# HammondWizard.net
KiCad netlist of a schematic drawn in EAGLE
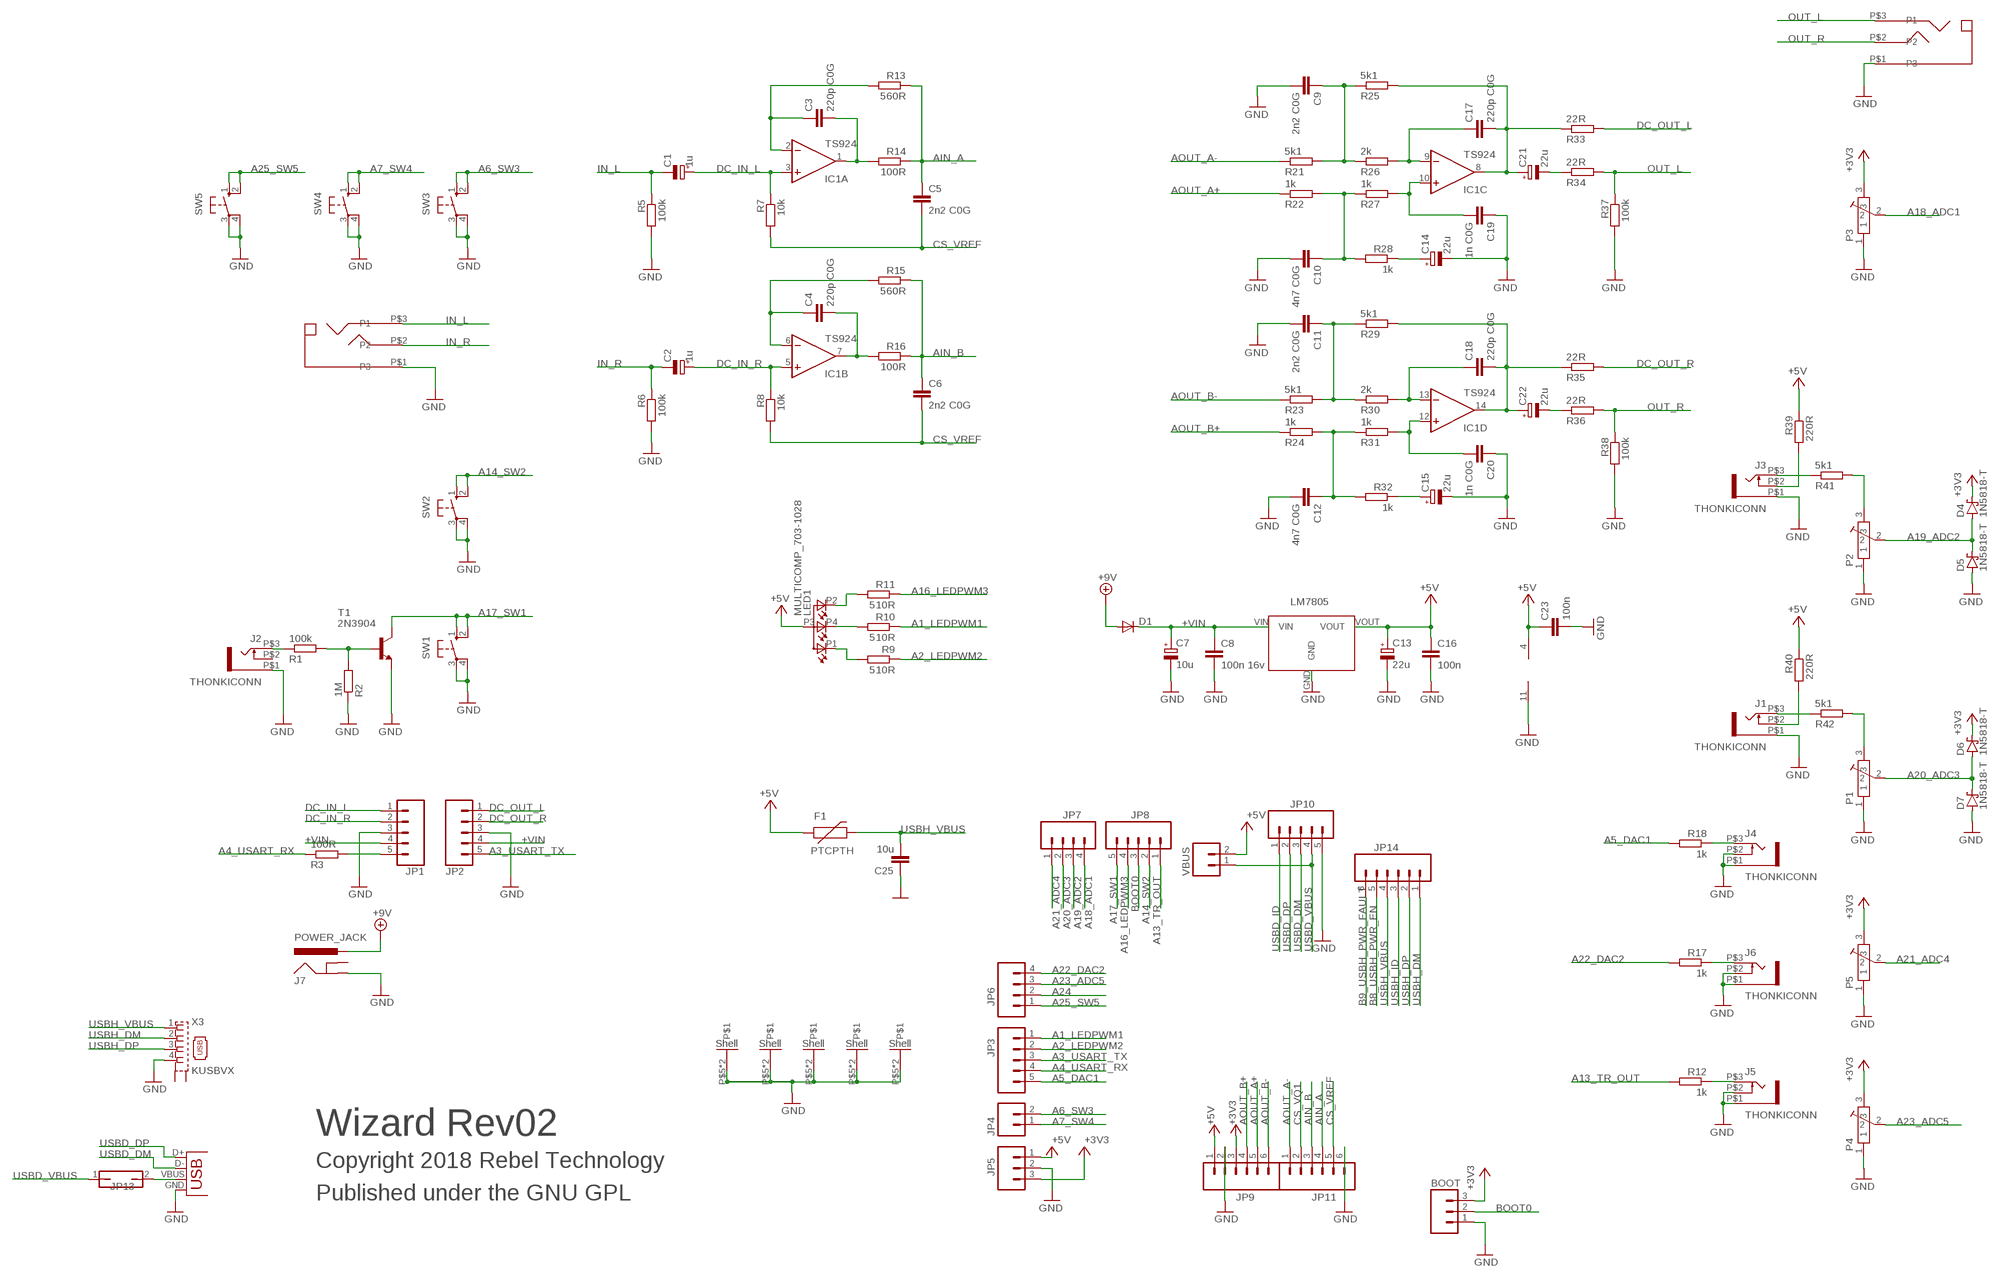
[diagram p0: schematic, sheet 1]

(export (version "E")
  (design (tool "Eeschema 10.0.6"))
  (components
    (comp (ref "BOOT")
      (value "M03PTH")
      (footprint "eagle-import:1X03")
      (libsource (lib "eagle-import") (part "M03PTH"))
    )
    (comp (ref "C1")
      (value "1u")
      (footprint "eagle-import:E5-6")
      (libsource (lib "eagle-import") (part "CPOL-EUE5-6"))
    )
    (comp (ref "C2")
      (value "1u")
      (footprint "eagle-import:E5-6")
      (libsource (lib "eagle-import") (part "CPOL-EUE5-6"))
    )
    (comp (ref "C3")
      (value "220p C0G")
      (footprint "eagle-import:C050-024X044")
      (libsource (lib "eagle-import") (part "resistor_C-EU050-024X044"))
    )
    (comp (ref "C4")
      (value "220p C0G")
      (footprint "eagle-import:C050-024X044")
      (libsource (lib "eagle-import") (part "resistor_C-EU050-024X044"))
    )
    (comp (ref "C5")
      (value "2n2 C0G")
      (footprint "eagle-import:C050-024X044")
      (libsource (lib "eagle-import") (part "resistor_C-EU050-024X044"))
    )
    (comp (ref "C6")
      (value "2n2 C0G")
      (footprint "eagle-import:C050-024X044")
      (libsource (lib "eagle-import") (part "resistor_C-EU050-024X044"))
    )
    (comp (ref "C7")
      (value "10u")
      (footprint "eagle-import:E5-6")
      (libsource (lib "eagle-import") (part "CPOL-EUE5-6"))
    )
    (comp (ref "C8")
      (value "100n 16v")
      (footprint "eagle-import:C050-024X044")
      (libsource (lib "eagle-import") (part "C-EU050-024X044"))
    )
    (comp (ref "C9")
      (value "2n2 C0G")
      (footprint "eagle-import:C050-024X044")
      (libsource (lib "eagle-import") (part "resistor_C-EU050-024X044"))
    )
    (comp (ref "C10")
      (value "4n7 C0G")
      (footprint "eagle-import:C050-024X044")
      (libsource (lib "eagle-import") (part "resistor_C-EU050-024X044"))
    )
    (comp (ref "C11")
      (value "2n2 C0G")
      (footprint "eagle-import:C050-024X044")
      (libsource (lib "eagle-import") (part "resistor_C-EU050-024X044"))
    )
    (comp (ref "C12")
      (value "4n7 C0G")
      (footprint "eagle-import:C050-024X044")
      (libsource (lib "eagle-import") (part "resistor_C-EU050-024X044"))
    )
    (comp (ref "C13")
      (value "22u")
      (footprint "eagle-import:E5-6")
      (libsource (lib "eagle-import") (part "CPOL-EUE5-6"))
    )
    (comp (ref "C14")
      (value "22u")
      (footprint "eagle-import:E5-6")
      (libsource (lib "eagle-import") (part "CPOL-EUE5-6"))
    )
    (comp (ref "C15")
      (value "22u")
      (footprint "eagle-import:E5-6")
      (libsource (lib "eagle-import") (part "CPOL-EUE5-6"))
    )
    (comp (ref "C16")
      (value "100n")
      (footprint "eagle-import:C050-024X044")
      (libsource (lib "eagle-import") (part "C-EU050-024X044"))
    )
    (comp (ref "C17")
      (value "220p C0G")
      (footprint "eagle-import:C050-024X044")
      (libsource (lib "eagle-import") (part "resistor_C-EU050-024X044"))
    )
    (comp (ref "C18")
      (value "220p C0G")
      (footprint "eagle-import:C050-024X044")
      (libsource (lib "eagle-import") (part "resistor_C-EU050-024X044"))
    )
    (comp (ref "C19")
      (value "1n C0G")
      (footprint "eagle-import:C050-024X044")
      (libsource (lib "eagle-import") (part "resistor_C-EU050-024X044"))
    )
    (comp (ref "C20")
      (value "1n C0G")
      (footprint "eagle-import:C050-024X044")
      (libsource (lib "eagle-import") (part "resistor_C-EU050-024X044"))
    )
    (comp (ref "C21")
      (value "22u")
      (footprint "eagle-import:E5-6")
      (libsource (lib "eagle-import") (part "CPOL-EUE5-6"))
    )
    (comp (ref "C22")
      (value "22u")
      (footprint "eagle-import:E5-6")
      (libsource (lib "eagle-import") (part "CPOL-EUE5-6"))
    )
    (comp (ref "C23")
      (value "100n")
      (footprint "eagle-import:C050-024X044")
      (libsource (lib "eagle-import") (part "resistor_C-EU050-024X044"))
    )
    (comp (ref "C25")
      (value "10u")
      (footprint "eagle-import:C050-024X044")
      (libsource (lib "eagle-import") (part "resistor_C-EU050-024X044"))
    )
    (comp (ref "D1")
      (value "DIODE1N4001")
      (footprint "eagle-import:DIODE-1N4001")
      (libsource (lib "eagle-import") (part "DIODE1N4001"))
    )
    (comp (ref "D4")
      (value "1N5818-T")
      (footprint "eagle-import:DO41-7.6")
      (libsource (lib "eagle-import") (part "1N5818-T"))
    )
    (comp (ref "D5")
      (value "1N5818-T")
      (footprint "eagle-import:DO41-7.6")
      (libsource (lib "eagle-import") (part "1N5818-T"))
    )
    (comp (ref "D6")
      (value "1N5818-T")
      (footprint "eagle-import:DO41-7.6")
      (libsource (lib "eagle-import") (part "1N5818-T"))
    )
    (comp (ref "D7")
      (value "1N5818-T")
      (footprint "eagle-import:DO41-7.6")
      (libsource (lib "eagle-import") (part "1N5818-T"))
    )
    (comp (ref "F1")
      (value "PTCPTH")
      (footprint "eagle-import:PTC")
      (libsource (lib "eagle-import") (part "PTCPTH"))
    )
    (comp (ref "IC1")
      (value "TS924")
      (footprint "eagle-import:DIL14")
      (libsource (lib "eagle-import") (part "LM324N"))
    )
    (comp (ref "J1")
      (value "THONKICONN")
      (footprint "eagle-import:THONKICONN")
      (libsource (lib "eagle-import") (part "THONKICONN"))
    )
    (comp (ref "J2")
      (value "THONKICONN")
      (footprint "eagle-import:THONKICONN")
      (libsource (lib "eagle-import") (part "THONKICONN"))
    )
    (comp (ref "J3")
      (value "THONKICONN")
      (footprint "eagle-import:THONKICONN")
      (libsource (lib "eagle-import") (part "THONKICONN"))
    )
    (comp (ref "J4")
      (value "THONKICONN")
      (footprint "eagle-import:THONKICONN")
      (libsource (lib "eagle-import") (part "THONKICONN"))
    )
    (comp (ref "J5")
      (value "THONKICONN")
      (footprint "eagle-import:THONKICONN")
      (libsource (lib "eagle-import") (part "THONKICONN"))
    )
    (comp (ref "J6")
      (value "THONKICONN")
      (footprint "eagle-import:THONKICONN")
      (libsource (lib "eagle-import") (part "THONKICONN"))
    )
    (comp (ref "J7")
      (value "POWER_JACK")
      (footprint "eagle-import:DC_JACK_SLOT")
      (libsource (lib "eagle-import") (part "POWER_JACK"))
    )
    (comp (ref "JP1")
      (value "CONN_05JST-VERT")
      (footprint "eagle-import:JST-5-PTH-VERT")
      (libsource (lib "eagle-import") (part "CONN_05JST-VERT"))
    )
    (comp (ref "JP2")
      (value "CONN_05JST-VERT")
      (footprint "eagle-import:JST-5-PTH-VERT")
      (libsource (lib "eagle-import") (part "CONN_05JST-VERT"))
    )
    (comp (ref "JP3")
      (value "M05PTH")
      (footprint "eagle-import:1X05")
      (libsource (lib "eagle-import") (part "M05PTH"))
    )
    (comp (ref "JP4")
      (value "M02PTH")
      (footprint "eagle-import:1X02")
      (libsource (lib "eagle-import") (part "M02PTH"))
    )
    (comp (ref "JP5")
      (value "M03PTH")
      (footprint "eagle-import:1X03")
      (libsource (lib "eagle-import") (part "M03PTH"))
    )
    (comp (ref "JP6")
      (value "M04PTH")
      (footprint "eagle-import:1X04")
      (libsource (lib "eagle-import") (part "M04PTH"))
    )
    (comp (ref "JP7")
      (value "M04PTH")
      (footprint "eagle-import:1X04")
      (libsource (lib "eagle-import") (part "M04PTH"))
    )
    (comp (ref "JP8")
      (value "M05PTH")
      (footprint "eagle-import:1X05")
      (libsource (lib "eagle-import") (part "M05PTH"))
    )
    (comp (ref "JP9")
      (value "M06SIP")
      (footprint "eagle-import:1X06")
      (libsource (lib "eagle-import") (part "M06SIP"))
    )
    (comp (ref "JP10")
      (value "M05PTH")
      (footprint "eagle-import:1X05")
      (libsource (lib "eagle-import") (part "M05PTH"))
    )
    (comp (ref "JP11")
      (value "M06SIP")
      (footprint "eagle-import:1X06")
      (libsource (lib "eagle-import") (part "M06SIP"))
    )
    (comp (ref "JP13")
      (value "JP1Q")
      (footprint "eagle-import:JP1")
      (libsource (lib "eagle-import") (part "JP1Q"))
    )
    (comp (ref "JP14")
      (value "M06SIP")
      (footprint "eagle-import:1X06")
      (libsource (lib "eagle-import") (part "M06SIP"))
    )
    (comp (ref "LED1")
      (value "MULTICOMP_703-1028")
      (footprint "eagle-import:RGB-LED-703-1028")
      (libsource (lib "eagle-import") (part "MULTICOMP_703-1028"))
    )
    (comp (ref "P1")
      (value "POT-ALPS-RK09L1140")
      (footprint "eagle-import:POT-ALPS-RK09L1140")
      (libsource (lib "eagle-import") (part "POT-ALPS-RK09L1140"))
    )
    (comp (ref "P2")
      (value "POT-ALPS-RK09L1140")
      (footprint "eagle-import:POT-ALPS-RK09L1140")
      (libsource (lib "eagle-import") (part "POT-ALPS-RK09L1140"))
    )
    (comp (ref "P3")
      (value "POT-ALPS-RK09L1140")
      (footprint "eagle-import:POT-ALPS-RK09L1140")
      (libsource (lib "eagle-import") (part "POT-ALPS-RK09L1140"))
    )
    (comp (ref "P4")
      (value "POT-ALPS-RK09L1140")
      (footprint "eagle-import:POT-ALPS-RK09L1140")
      (libsource (lib "eagle-import") (part "POT-ALPS-RK09L1140"))
    )
    (comp (ref "P5")
      (value "POT-ALPS-RK09L1140")
      (footprint "eagle-import:POT-ALPS-RK09L1140")
      (libsource (lib "eagle-import") (part "POT-ALPS-RK09L1140"))
    )
    (comp (ref "R1")
      (value "100k")
      (footprint "eagle-import:0204_7")
      (libsource (lib "eagle-import") (part "R-EU_0204/7"))
    )
    (comp (ref "R2")
      (value "1M")
      (footprint "eagle-import:0204_7")
      (libsource (lib "eagle-import") (part "R-EU_0204/7"))
    )
    (comp (ref "R3")
      (value "100R")
      (footprint "eagle-import:0204_7")
      (libsource (lib "eagle-import") (part "R-EU_0204/7"))
    )
    (comp (ref "R5")
      (value "100k")
      (footprint "eagle-import:0204_7")
      (libsource (lib "eagle-import") (part "R-EU_0204/7"))
    )
    (comp (ref "R6")
      (value "100k")
      (footprint "eagle-import:0204_7")
      (libsource (lib "eagle-import") (part "R-EU_0204/7"))
    )
    (comp (ref "R7")
      (value "10k")
      (footprint "eagle-import:0204_7")
      (libsource (lib "eagle-import") (part "R-EU_0204/7"))
    )
    (comp (ref "R8")
      (value "10k")
      (footprint "eagle-import:0204_7")
      (libsource (lib "eagle-import") (part "R-EU_0204/7"))
    )
    (comp (ref "R9")
      (value "510R")
      (footprint "eagle-import:0204_7")
      (libsource (lib "eagle-import") (part "R-EU_0204/7"))
    )
    (comp (ref "R10")
      (value "510R")
      (footprint "eagle-import:0204_7")
      (libsource (lib "eagle-import") (part "R-EU_0204/7"))
    )
    (comp (ref "R11")
      (value "510R")
      (footprint "eagle-import:0204_7")
      (libsource (lib "eagle-import") (part "R-EU_0204/7"))
    )
    (comp (ref "R12")
      (value "1k")
      (footprint "eagle-import:0204_7")
      (libsource (lib "eagle-import") (part "R-EU_0204/7"))
    )
    (comp (ref "R13")
      (value "560R")
      (footprint "eagle-import:0204_7")
      (libsource (lib "eagle-import") (part "R-EU_0204/7"))
    )
    (comp (ref "R14")
      (value "100R")
      (footprint "eagle-import:0204_7")
      (libsource (lib "eagle-import") (part "R-EU_0204/7"))
    )
    (comp (ref "R15")
      (value "560R")
      (footprint "eagle-import:0204_7")
      (libsource (lib "eagle-import") (part "R-EU_0204/7"))
    )
    (comp (ref "R16")
      (value "100R")
      (footprint "eagle-import:0204_7")
      (libsource (lib "eagle-import") (part "R-EU_0204/7"))
    )
    (comp (ref "R17")
      (value "1k")
      (footprint "eagle-import:0204_7")
      (libsource (lib "eagle-import") (part "R-EU_0204/7"))
    )
    (comp (ref "R18")
      (value "1k")
      (footprint "eagle-import:0204_7")
      (libsource (lib "eagle-import") (part "R-EU_0204/7"))
    )
    (comp (ref "R21")
      (value "5k1")
      (footprint "eagle-import:0204_7")
      (libsource (lib "eagle-import") (part "R-EU_0204/7"))
    )
    (comp (ref "R22")
      (value "1k")
      (footprint "eagle-import:0204_7")
      (libsource (lib "eagle-import") (part "R-EU_0204/7"))
    )
    (comp (ref "R23")
      (value "5k1")
      (footprint "eagle-import:0204_7")
      (libsource (lib "eagle-import") (part "R-EU_0204/7"))
    )
    (comp (ref "R24")
      (value "1k")
      (footprint "eagle-import:0204_7")
      (libsource (lib "eagle-import") (part "R-EU_0204/7"))
    )
    (comp (ref "R25")
      (value "5k1")
      (footprint "eagle-import:0204_7")
      (libsource (lib "eagle-import") (part "R-EU_0204/7"))
    )
    (comp (ref "R26")
      (value "2k")
      (footprint "eagle-import:0204_7")
      (libsource (lib "eagle-import") (part "R-EU_0204/7"))
    )
    (comp (ref "R27")
      (value "1k")
      (footprint "eagle-import:0204_7")
      (libsource (lib "eagle-import") (part "R-EU_0204/7"))
    )
    (comp (ref "R28")
      (value "1k")
      (footprint "eagle-import:0204_7")
      (libsource (lib "eagle-import") (part "R-EU_0204/7"))
    )
    (comp (ref "R29")
      (value "5k1")
      (footprint "eagle-import:0204_7")
      (libsource (lib "eagle-import") (part "R-EU_0204/7"))
    )
    (comp (ref "R30")
      (value "2k")
      (footprint "eagle-import:0204_7")
      (libsource (lib "eagle-import") (part "R-EU_0204/7"))
    )
    (comp (ref "R31")
      (value "1k")
      (footprint "eagle-import:0204_7")
      (libsource (lib "eagle-import") (part "R-EU_0204/7"))
    )
    (comp (ref "R32")
      (value "1k")
      (footprint "eagle-import:0204_7")
      (libsource (lib "eagle-import") (part "R-EU_0204/7"))
    )
    (comp (ref "R33")
      (value "22R")
      (footprint "eagle-import:0204_7")
      (libsource (lib "eagle-import") (part "R-EU_0204/7"))
    )
    (comp (ref "R34")
      (value "22R")
      (footprint "eagle-import:0204_7")
      (libsource (lib "eagle-import") (part "R-EU_0204/7"))
    )
    (comp (ref "R35")
      (value "22R")
      (footprint "eagle-import:0204_7")
      (libsource (lib "eagle-import") (part "R-EU_0204/7"))
    )
    (comp (ref "R36")
      (value "22R")
      (footprint "eagle-import:0204_7")
      (libsource (lib "eagle-import") (part "R-EU_0204/7"))
    )
    (comp (ref "R37")
      (value "100k")
      (footprint "eagle-import:0204_7")
      (libsource (lib "eagle-import") (part "R-EU_0204/7"))
    )
    (comp (ref "R38")
      (value "100k")
      (footprint "eagle-import:0204_7")
      (libsource (lib "eagle-import") (part "R-EU_0204/7"))
    )
    (comp (ref "R39")
      (value "220R")
      (footprint "eagle-import:0204_7")
      (libsource (lib "eagle-import") (part "R-EU_0204/7"))
    )
    (comp (ref "R40")
      (value "220R")
      (footprint "eagle-import:0204_7")
      (libsource (lib "eagle-import") (part "R-EU_0204/7"))
    )
    (comp (ref "R41")
      (value "5k1")
      (footprint "eagle-import:0204_7")
      (libsource (lib "eagle-import") (part "R-EU_0204/7"))
    )
    (comp (ref "R42")
      (value "5k1")
      (footprint "eagle-import:0204_7")
      (libsource (lib "eagle-import") (part "R-EU_0204/7"))
    )
    (comp (ref "SW1")
      (value "10-XX")
      (footprint "eagle-import:B3F-10XX")
      (fields (field (name "MPN") "B3F-1000"))
      (libsource (lib "eagle-import") (part "10-XX"))
    )
    (comp (ref "SW2")
      (value "10-XX")
      (footprint "eagle-import:B3F-10XX")
      (fields (field (name "MPN") "B3F-1000"))
      (libsource (lib "eagle-import") (part "10-XX"))
    )
    (comp (ref "SW3")
      (value "10-XX")
      (footprint "eagle-import:B3F-10XX")
      (fields (field (name "MPN") "B3F-1000"))
      (libsource (lib "eagle-import") (part "10-XX"))
    )
    (comp (ref "SW4")
      (value "10-XX")
      (footprint "eagle-import:B3F-10XX")
      (fields (field (name "MPN") "B3F-1000"))
      (libsource (lib "eagle-import") (part "10-XX"))
    )
    (comp (ref "SW5")
      (value "10-XX")
      (footprint "eagle-import:B3F-10XX")
      (fields (field (name "MPN") "B3F-1000"))
      (libsource (lib "eagle-import") (part "10-XX"))
    )
    (comp (ref "T1")
      (value "2N3904")
      (footprint "eagle-import:TO92")
      (libsource (lib "eagle-import") (part "2N3904"))
    )
    (comp (ref "U$4")
      (value "THONKICONN_STEREO")
      (footprint "eagle-import:THONKICONN_STEREO")
      (libsource (lib "eagle-import") (part "THONKICONN_STEREO"))
    )
    (comp (ref "U$5")
      (value "THONKICONN_STEREO")
      (footprint "eagle-import:THONKICONN_STEREO")
      (libsource (lib "eagle-import") (part "THONKICONN_STEREO"))
    )
    (comp (ref "U2")
      (value "LM7805")
      (footprint "eagle-import:REG_S9V11F5")
      (libsource (lib "eagle-import") (part "REG_S9V11F5"))
    )
    (comp (ref "VBUS")
      (value "M02PTH")
      (footprint "eagle-import:1X02")
      (libsource (lib "eagle-import") (part "M02PTH"))
    )
    (comp (ref "X3")
      (value "KUSBVX")
      (footprint "eagle-import:KUSBVX")
      (libsource (lib "eagle-import") (part "KUSBVX"))
    )
    (comp (ref "X5")
      (value "USBPTH-VERTICAL")
      (footprint "eagle-import:USB-B-PTH-VERTICAL")
      (libsource (lib "eagle-import") (part "USBPTH-VERTICAL"))
    )
  )
  (nets
    (net (code "1") (name "+3V3") (class "Default")
      (node (ref "BOOT") (pin "3") (pinfunction "3_3") (pintype "passive"))
      (node (ref "D4") (pin "C") (pinfunction "C_C") (pintype "passive"))
      (node (ref "D6") (pin "C") (pinfunction "C_C") (pintype "passive"))
      (node (ref "JP5") (pin "3") (pinfunction "3_3") (pintype "passive"))
      (node (ref "JP9") (pin "3") (pinfunction "3_3") (pintype "passive"))
      (node (ref "P3") (pin "3") (pinfunction "3_3") (pintype "bidirectional"))
      (node (ref "P4") (pin "3") (pinfunction "3_3") (pintype "bidirectional"))
      (node (ref "P5") (pin "3") (pinfunction "3_3") (pintype "bidirectional"))
    )
    (net (code "2") (name "+5V") (class "Default")
      (node (ref "C13") (pin "+") (pinfunction "+_+") (pintype "passive"))
      (node (ref "C16") (pin "1") (pinfunction "1_1") (pintype "passive"))
      (node (ref "C23") (pin "1") (pinfunction "1_1") (pintype "passive"))
      (node (ref "F1") (pin "P$1") (pinfunction "1_P$1") (pintype "bidirectional"))
      (node (ref "IC1") (pin "4") (pinfunction "V+_4") (pintype "power_in"))
      (node (ref "JP5") (pin "1") (pinfunction "1_1") (pintype "passive"))
      (node (ref "JP9") (pin "1") (pinfunction "1_1") (pintype "passive"))
      (node (ref "LED1") (pin "P3") (pinfunction "A_P3") (pintype "passive"))
      (node (ref "R39") (pin "1") (pinfunction "1_1") (pintype "passive"))
      (node (ref "R40") (pin "1") (pinfunction "1_1") (pintype "passive"))
      (node (ref "U2") (pin "VOUT") (pinfunction "VOUT_VOUT") (pintype "output"))
      (node (ref "VBUS") (pin "2") (pinfunction "2_2") (pintype "passive"))
    )
    (net (code "3") (name "+9V") (class "Default")
      (node (ref "D1") (pin "A") (pinfunction "A_A") (pintype "passive"))
      (node (ref "J7") (pin "PWR") (pinfunction "PWR_PWR") (pintype "bidirectional"))
    )
    (net (code "4") (name "/+VIN") (class "Default")
      (node (ref "C7") (pin "+") (pinfunction "+_+") (pintype "passive"))
      (node (ref "C8") (pin "1") (pinfunction "1_1") (pintype "passive"))
      (node (ref "D1") (pin "C") (pinfunction "C_C") (pintype "passive"))
      (node (ref "JP1") (pin "4") (pinfunction "4_4") (pintype "passive"))
      (node (ref "JP2") (pin "4") (pinfunction "4_4") (pintype "passive"))
      (node (ref "U2") (pin "VIN") (pinfunction "VIN_VIN") (pintype "input"))
    )
    (net (code "5") (name "/A1_LEDPWM1") (class "Default")
      (node (ref "JP3") (pin "1") (pinfunction "1_1") (pintype "passive"))
      (node (ref "R10") (pin "1") (pinfunction "1_1") (pintype "passive"))
    )
    (net (code "6") (name "/A2_LEDPWM2") (class "Default")
      (node (ref "JP3") (pin "2") (pinfunction "2_2") (pintype "passive"))
      (node (ref "R9") (pin "1") (pinfunction "1_1") (pintype "passive"))
    )
    (net (code "7") (name "/A3_USART_TX") (class "Default")
      (node (ref "JP2") (pin "5") (pinfunction "5_5") (pintype "passive"))
      (node (ref "JP3") (pin "3") (pinfunction "3_3") (pintype "passive"))
    )
    (net (code "8") (name "/A4_USART_RX") (class "Default")
      (node (ref "JP3") (pin "4") (pinfunction "4_4") (pintype "passive"))
      (node (ref "R3") (pin "1") (pinfunction "1_1") (pintype "passive"))
    )
    (net (code "9") (name "/A5_DAC1") (class "Default")
      (node (ref "JP3") (pin "5") (pinfunction "5_5") (pintype "passive"))
      (node (ref "R18") (pin "2") (pinfunction "2_2") (pintype "passive"))
    )
    (net (code "10") (name "/A6_SW3") (class "Default")
      (node (ref "JP4") (pin "2") (pinfunction "2_2") (pintype "passive"))
      (node (ref "SW3") (pin "1") (pinfunction "S_1") (pintype "passive"))
      (node (ref "SW3") (pin "2") (pinfunction "S1_2") (pintype "passive"))
    )
    (net (code "11") (name "/A7_SW4") (class "Default")
      (node (ref "JP4") (pin "1") (pinfunction "1_1") (pintype "passive"))
      (node (ref "SW4") (pin "1") (pinfunction "S_1") (pintype "passive"))
      (node (ref "SW4") (pin "2") (pinfunction "S1_2") (pintype "passive"))
    )
    (net (code "12") (name "/A13_TR_OUT") (class "Default")
      (node (ref "JP8") (pin "1") (pinfunction "1_1") (pintype "passive"))
      (node (ref "R12") (pin "2") (pinfunction "2_2") (pintype "passive"))
    )
    (net (code "13") (name "/A14_SW2") (class "Default")
      (node (ref "JP8") (pin "2") (pinfunction "2_2") (pintype "passive"))
      (node (ref "SW2") (pin "1") (pinfunction "S_1") (pintype "passive"))
      (node (ref "SW2") (pin "2") (pinfunction "S1_2") (pintype "passive"))
    )
    (net (code "14") (name "/A16_LEDPWM3") (class "Default")
      (node (ref "JP8") (pin "4") (pinfunction "4_4") (pintype "passive"))
      (node (ref "R11") (pin "1") (pinfunction "1_1") (pintype "passive"))
    )
    (net (code "15") (name "/A17_SW1") (class "Default")
      (node (ref "JP8") (pin "5") (pinfunction "5_5") (pintype "passive"))
      (node (ref "SW1") (pin "1") (pinfunction "S_1") (pintype "passive"))
      (node (ref "SW1") (pin "2") (pinfunction "S1_2") (pintype "passive"))
      (node (ref "T1") (pin "1") (pinfunction "C_1") (pintype "passive"))
    )
    (net (code "16") (name "/A18_ADC1") (class "Default")
      (node (ref "JP7") (pin "4") (pinfunction "4_4") (pintype "passive"))
      (node (ref "P3") (pin "2") (pinfunction "2_2") (pintype "bidirectional"))
    )
    (net (code "17") (name "/A19_ADC2") (class "Default")
      (node (ref "D4") (pin "A") (pinfunction "A_A") (pintype "passive"))
      (node (ref "D5") (pin "C") (pinfunction "C_C") (pintype "passive"))
      (node (ref "JP7") (pin "3") (pinfunction "3_3") (pintype "passive"))
      (node (ref "P2") (pin "2") (pinfunction "2_2") (pintype "bidirectional"))
    )
    (net (code "18") (name "/A20_ADC3") (class "Default")
      (node (ref "D6") (pin "A") (pinfunction "A_A") (pintype "passive"))
      (node (ref "D7") (pin "C") (pinfunction "C_C") (pintype "passive"))
      (node (ref "JP7") (pin "2") (pinfunction "2_2") (pintype "passive"))
      (node (ref "P1") (pin "2") (pinfunction "2_2") (pintype "bidirectional"))
    )
    (net (code "19") (name "/A21_ADC4") (class "Default")
      (node (ref "JP7") (pin "1") (pinfunction "1_1") (pintype "passive"))
      (node (ref "P5") (pin "2") (pinfunction "2_2") (pintype "bidirectional"))
    )
    (net (code "20") (name "/A22_DAC2") (class "Default")
      (node (ref "JP6") (pin "4") (pinfunction "4_4") (pintype "passive"))
      (node (ref "R17") (pin "2") (pinfunction "2_2") (pintype "passive"))
    )
    (net (code "21") (name "/A23_ADC5") (class "Default")
      (node (ref "JP6") (pin "3") (pinfunction "3_3") (pintype "passive"))
      (node (ref "P4") (pin "2") (pinfunction "2_2") (pintype "bidirectional"))
    )
    (net (code "22") (name "/A24") (class "Default")
      (node (ref "JP6") (pin "2") (pinfunction "2_2") (pintype "passive"))
    )
    (net (code "23") (name "/A25_SW5") (class "Default")
      (node (ref "JP6") (pin "1") (pinfunction "1_1") (pintype "passive"))
      (node (ref "SW5") (pin "1") (pinfunction "S_1") (pintype "passive"))
      (node (ref "SW5") (pin "2") (pinfunction "S1_2") (pintype "passive"))
    )
    (net (code "24") (name "/AIN_A") (class "Default")
      (node (ref "C5") (pin "1") (pinfunction "1_1") (pintype "passive"))
      (node (ref "JP11") (pin "4") (pinfunction "4_4") (pintype "passive"))
      (node (ref "R13") (pin "1") (pinfunction "1_1") (pintype "passive"))
      (node (ref "R14") (pin "1") (pinfunction "1_1") (pintype "passive"))
    )
    (net (code "25") (name "/AIN_B") (class "Default")
      (node (ref "C6") (pin "1") (pinfunction "1_1") (pintype "passive"))
      (node (ref "JP11") (pin "3") (pinfunction "3_3") (pintype "passive"))
      (node (ref "R15") (pin "1") (pinfunction "1_1") (pintype "passive"))
      (node (ref "R16") (pin "1") (pinfunction "1_1") (pintype "passive"))
    )
    (net (code "26") (name "/AOUT_A+") (class "Default")
      (node (ref "JP9") (pin "5") (pinfunction "5_5") (pintype "passive"))
      (node (ref "R22") (pin "1") (pinfunction "1_1") (pintype "passive"))
    )
    (net (code "27") (name "/AOUT_A-") (class "Default")
      (node (ref "JP11") (pin "1") (pinfunction "1_1") (pintype "passive"))
      (node (ref "R21") (pin "1") (pinfunction "1_1") (pintype "passive"))
    )
    (net (code "28") (name "/AOUT_B+") (class "Default")
      (node (ref "JP9") (pin "4") (pinfunction "4_4") (pintype "passive"))
      (node (ref "R24") (pin "1") (pinfunction "1_1") (pintype "passive"))
    )
    (net (code "29") (name "/AOUT_B-") (class "Default")
      (node (ref "JP9") (pin "6") (pinfunction "6_6") (pintype "passive"))
      (node (ref "R23") (pin "1") (pinfunction "1_1") (pintype "passive"))
    )
    (net (code "30") (name "/B8_USBH_PWR_EN") (class "Default")
      (node (ref "JP14") (pin "5") (pinfunction "5_5") (pintype "passive"))
    )
    (net (code "31") (name "/B9_USBH_PWR_FAULT") (class "Default")
      (node (ref "JP14") (pin "6") (pinfunction "6_6") (pintype "passive"))
    )
    (net (code "32") (name "/BOOT0") (class "Default")
      (node (ref "BOOT") (pin "2") (pinfunction "2_2") (pintype "passive"))
      (node (ref "JP8") (pin "3") (pinfunction "3_3") (pintype "passive"))
    )
    (net (code "33") (name "/CS_VQ1") (class "Default")
      (node (ref "JP11") (pin "2") (pinfunction "2_2") (pintype "passive"))
    )
    (net (code "34") (name "/CS_VREF") (class "Default")
      (node (ref "C5") (pin "2") (pinfunction "2_2") (pintype "passive"))
      (node (ref "C6") (pin "2") (pinfunction "2_2") (pintype "passive"))
      (node (ref "JP11") (pin "5") (pinfunction "5_5") (pintype "passive"))
      (node (ref "R7") (pin "2") (pinfunction "2_2") (pintype "passive"))
      (node (ref "R8") (pin "2") (pinfunction "2_2") (pintype "passive"))
    )
    (net (code "35") (name "/DC_IN_L") (class "Default")
      (node (ref "C1") (pin "+") (pinfunction "+_+") (pintype "passive"))
      (node (ref "IC1") (pin "3") (pinfunction "+IN_3") (pintype "input"))
      (node (ref "JP1") (pin "1") (pinfunction "1_1") (pintype "passive"))
      (node (ref "R7") (pin "1") (pinfunction "1_1") (pintype "passive"))
    )
    (net (code "36") (name "/DC_IN_R") (class "Default")
      (node (ref "C2") (pin "+") (pinfunction "+_+") (pintype "passive"))
      (node (ref "IC1") (pin "5") (pinfunction "+IN_5") (pintype "input"))
      (node (ref "JP1") (pin "2") (pinfunction "2_2") (pintype "passive"))
      (node (ref "R8") (pin "1") (pinfunction "1_1") (pintype "passive"))
    )
    (net (code "37") (name "/DC_OUT_L") (class "Default")
      (node (ref "JP2") (pin "1") (pinfunction "1_1") (pintype "passive"))
      (node (ref "R33") (pin "2") (pinfunction "2_2") (pintype "passive"))
    )
    (net (code "38") (name "/DC_OUT_R") (class "Default")
      (node (ref "JP2") (pin "2") (pinfunction "2_2") (pintype "passive"))
      (node (ref "R35") (pin "2") (pinfunction "2_2") (pintype "passive"))
    )
    (net (code "39") (name "/IN_L") (class "Default")
      (node (ref "C1") (pin "-") (pinfunction "-_-") (pintype "passive"))
      (node (ref "R5") (pin "1") (pinfunction "1_1") (pintype "passive"))
      (node (ref "U$4") (pin "P$3") (pinfunction "P1_P$3") (pintype "bidirectional"))
    )
    (net (code "40") (name "/IN_R") (class "Default")
      (node (ref "C2") (pin "-") (pinfunction "-_-") (pintype "passive"))
      (node (ref "R6") (pin "1") (pinfunction "1_1") (pintype "passive"))
      (node (ref "U$4") (pin "P$2") (pinfunction "P2_P$2") (pintype "bidirectional"))
    )
    (net (code "41") (name "/OUT_L") (class "Default")
      (node (ref "R34") (pin "2") (pinfunction "2_2") (pintype "passive"))
      (node (ref "R37") (pin "1") (pinfunction "1_1") (pintype "passive"))
      (node (ref "U$5") (pin "P$3") (pinfunction "P1_P$3") (pintype "bidirectional"))
    )
    (net (code "42") (name "/OUT_R") (class "Default")
      (node (ref "R36") (pin "2") (pinfunction "2_2") (pintype "passive"))
      (node (ref "R38") (pin "1") (pinfunction "1_1") (pintype "passive"))
      (node (ref "U$5") (pin "P$2") (pinfunction "P2_P$2") (pintype "bidirectional"))
    )
    (net (code "43") (name "/USBD_DM") (class "Default")
      (node (ref "JP10") (pin "3") (pinfunction "3_3") (pintype "passive"))
      (node (ref "X5") (pin "D-") (pinfunction "D-_D-") (pintype "bidirectional"))
    )
    (net (code "44") (name "/USBD_DP") (class "Default")
      (node (ref "JP10") (pin "2") (pinfunction "2_2") (pintype "passive"))
      (node (ref "X5") (pin "D+") (pinfunction "D+_D+") (pintype "bidirectional"))
    )
    (net (code "45") (name "/USBD_ID") (class "Default")
      (node (ref "JP10") (pin "1") (pinfunction "1_1") (pintype "passive"))
    )
    (net (code "46") (name "/USBD_VBUS") (class "Default")
      (node (ref "JP10") (pin "4") (pinfunction "4_4") (pintype "passive"))
      (node (ref "JP13") (pin "1") (pinfunction "1_1") (pintype "passive"))
      (node (ref "VBUS") (pin "1") (pinfunction "1_1") (pintype "passive"))
    )
    (net (code "47") (name "/USBH_DM") (class "Default")
      (node (ref "JP14") (pin "1") (pinfunction "1_1") (pintype "passive"))
      (node (ref "X3") (pin "2") (pinfunction "2_2") (pintype "passive"))
    )
    (net (code "48") (name "/USBH_DP") (class "Default")
      (node (ref "JP14") (pin "2") (pinfunction "2_2") (pintype "passive"))
      (node (ref "X3") (pin "3") (pinfunction "3_3") (pintype "passive"))
    )
    (net (code "49") (name "/USBH_ID") (class "Default")
      (node (ref "JP14") (pin "3") (pinfunction "3_3") (pintype "passive"))
    )
    (net (code "50") (name "/USBH_VBUS") (class "Default")
      (node (ref "C25") (pin "2") (pinfunction "2_2") (pintype "passive"))
      (node (ref "F1") (pin "P$2") (pinfunction "2_P$2") (pintype "bidirectional"))
      (node (ref "JP14") (pin "4") (pinfunction "4_4") (pintype "passive"))
      (node (ref "X3") (pin "1") (pinfunction "1_1") (pintype "passive"))
    )
    (net (code "51") (name "GND") (class "Default")
      (node (ref "BOOT") (pin "1") (pinfunction "1_1") (pintype "passive"))
      (node (ref "C10") (pin "2") (pinfunction "2_2") (pintype "passive"))
      (node (ref "C11") (pin "2") (pinfunction "2_2") (pintype "passive"))
      (node (ref "C12") (pin "2") (pinfunction "2_2") (pintype "passive"))
      (node (ref "C13") (pin "-") (pinfunction "-_-") (pintype "passive"))
      (node (ref "C14") (pin "-") (pinfunction "-_-") (pintype "passive"))
      (node (ref "C15") (pin "-") (pinfunction "-_-") (pintype "passive"))
      (node (ref "C16") (pin "2") (pinfunction "2_2") (pintype "passive"))
      (node (ref "C19") (pin "1") (pinfunction "1_1") (pintype "passive"))
      (node (ref "C20") (pin "1") (pinfunction "1_1") (pintype "passive"))
      (node (ref "C23") (pin "2") (pinfunction "2_2") (pintype "passive"))
      (node (ref "C25") (pin "1") (pinfunction "1_1") (pintype "passive"))
      (node (ref "C7") (pin "-") (pinfunction "-_-") (pintype "passive"))
      (node (ref "C8") (pin "2") (pinfunction "2_2") (pintype "passive"))
      (node (ref "C9") (pin "2") (pinfunction "2_2") (pintype "passive"))
      (node (ref "D5") (pin "A") (pinfunction "A_A") (pintype "passive"))
      (node (ref "D7") (pin "A") (pinfunction "A_A") (pintype "passive"))
      (node (ref "IC1") (pin "11") (pinfunction "V-_11") (pintype "power_in"))
      (node (ref "J1") (pin "P$1") (pinfunction "5_P$1") (pintype "passive"))
      (node (ref "J2") (pin "P$1") (pinfunction "5_P$1") (pintype "passive"))
      (node (ref "J3") (pin "P$1") (pinfunction "5_P$1") (pintype "passive"))
      (node (ref "J4") (pin "P$1") (pinfunction "5_P$1") (pintype "passive"))
      (node (ref "J4") (pin "P$2") (pinfunction "4_P$2") (pintype "passive"))
      (node (ref "J5") (pin "P$1") (pinfunction "5_P$1") (pintype "passive"))
      (node (ref "J5") (pin "P$2") (pinfunction "4_P$2") (pintype "passive"))
      (node (ref "J6") (pin "P$1") (pinfunction "5_P$1") (pintype "passive"))
      (node (ref "J6") (pin "P$2") (pinfunction "4_P$2") (pintype "passive"))
      (node (ref "J7") (pin "GND") (pinfunction "GND_GND") (pintype "bidirectional"))
      (node (ref "JP1") (pin "3") (pinfunction "3_3") (pintype "passive"))
      (node (ref "JP10") (pin "5") (pinfunction "5_5") (pintype "passive"))
      (node (ref "JP11") (pin "6") (pinfunction "6_6") (pintype "passive"))
      (node (ref "JP2") (pin "3") (pinfunction "3_3") (pintype "passive"))
      (node (ref "JP5") (pin "2") (pinfunction "2_2") (pintype "passive"))
      (node (ref "JP9") (pin "2") (pinfunction "2_2") (pintype "passive"))
      (node (ref "P1") (pin "1") (pinfunction "1_1") (pintype "bidirectional"))
      (node (ref "P1") (pin "P$5") (pinfunction "P$1_P$5") (pintype "bidirectional"))
      (node (ref "P1") (pin "P$6") (pinfunction "P$1_P$6") (pintype "bidirectional"))
      (node (ref "P2") (pin "1") (pinfunction "1_1") (pintype "bidirectional"))
      (node (ref "P2") (pin "P$5") (pinfunction "P$1_P$5") (pintype "bidirectional"))
      (node (ref "P2") (pin "P$6") (pinfunction "P$1_P$6") (pintype "bidirectional"))
      (node (ref "P3") (pin "1") (pinfunction "1_1") (pintype "bidirectional"))
      (node (ref "P3") (pin "P$5") (pinfunction "P$1_P$5") (pintype "bidirectional"))
      (node (ref "P3") (pin "P$6") (pinfunction "P$1_P$6") (pintype "bidirectional"))
      (node (ref "P4") (pin "1") (pinfunction "1_1") (pintype "bidirectional"))
      (node (ref "P4") (pin "P$5") (pinfunction "P$1_P$5") (pintype "bidirectional"))
      (node (ref "P4") (pin "P$6") (pinfunction "P$1_P$6") (pintype "bidirectional"))
      (node (ref "P5") (pin "1") (pinfunction "1_1") (pintype "bidirectional"))
      (node (ref "P5") (pin "P$5") (pinfunction "P$1_P$5") (pintype "bidirectional"))
      (node (ref "P5") (pin "P$6") (pinfunction "P$1_P$6") (pintype "bidirectional"))
      (node (ref "R2") (pin "1") (pinfunction "1_1") (pintype "passive"))
      (node (ref "R37") (pin "2") (pinfunction "2_2") (pintype "passive"))
      (node (ref "R38") (pin "2") (pinfunction "2_2") (pintype "passive"))
      (node (ref "R5") (pin "2") (pinfunction "2_2") (pintype "passive"))
      (node (ref "R6") (pin "2") (pinfunction "2_2") (pintype "passive"))
      (node (ref "SW1") (pin "3") (pinfunction "P_3") (pintype "passive"))
      (node (ref "SW1") (pin "4") (pinfunction "P1_4") (pintype "passive"))
      (node (ref "SW2") (pin "3") (pinfunction "P_3") (pintype "passive"))
      (node (ref "SW2") (pin "4") (pinfunction "P1_4") (pintype "passive"))
      (node (ref "SW3") (pin "3") (pinfunction "P_3") (pintype "passive"))
      (node (ref "SW3") (pin "4") (pinfunction "P1_4") (pintype "passive"))
      (node (ref "SW4") (pin "3") (pinfunction "P_3") (pintype "passive"))
      (node (ref "SW4") (pin "4") (pinfunction "P1_4") (pintype "passive"))
      (node (ref "SW5") (pin "3") (pinfunction "P_3") (pintype "passive"))
      (node (ref "SW5") (pin "4") (pinfunction "P1_4") (pintype "passive"))
      (node (ref "T1") (pin "3") (pinfunction "E_3") (pintype "passive"))
      (node (ref "U$4") (pin "P$1") (pinfunction "P3_P$1") (pintype "bidirectional"))
      (node (ref "U$5") (pin "P$1") (pinfunction "P3_P$1") (pintype "bidirectional"))
      (node (ref "U2") (pin "GND") (pinfunction "GND_GND") (pintype "power_in"))
      (node (ref "X3") (pin "4") (pinfunction "4_4") (pintype "passive"))
      (node (ref "X5") (pin "GND") (pinfunction "GND_GND") (pintype "bidirectional"))
    )
    (net (code "52") (name "Net-(C9-Pad1)") (class "Default")
      (node (ref "C9") (pin "1") (pinfunction "1_1") (pintype "passive"))
      (node (ref "R21") (pin "2") (pinfunction "2_2") (pintype "passive"))
      (node (ref "R25") (pin "1") (pinfunction "1_1") (pintype "passive"))
      (node (ref "R26") (pin "1") (pinfunction "1_1") (pintype "passive"))
    )
    (net (code "53") (name "Net-(C10-Pad1)") (class "Default")
      (node (ref "C10") (pin "1") (pinfunction "1_1") (pintype "passive"))
      (node (ref "R22") (pin "2") (pinfunction "2_2") (pintype "passive"))
      (node (ref "R27") (pin "1") (pinfunction "1_1") (pintype "passive"))
      (node (ref "R28") (pin "2") (pinfunction "2_2") (pintype "passive"))
    )
    (net (code "54") (name "Net-(C11-Pad1)") (class "Default")
      (node (ref "C11") (pin "1") (pinfunction "1_1") (pintype "passive"))
      (node (ref "R23") (pin "2") (pinfunction "2_2") (pintype "passive"))
      (node (ref "R29") (pin "1") (pinfunction "1_1") (pintype "passive"))
      (node (ref "R30") (pin "1") (pinfunction "1_1") (pintype "passive"))
    )
    (net (code "55") (name "Net-(C12-Pad1)") (class "Default")
      (node (ref "C12") (pin "1") (pinfunction "1_1") (pintype "passive"))
      (node (ref "R24") (pin "2") (pinfunction "2_2") (pintype "passive"))
      (node (ref "R31") (pin "1") (pinfunction "1_1") (pintype "passive"))
      (node (ref "R32") (pin "2") (pinfunction "2_2") (pintype "passive"))
    )
    (net (code "56") (name "Net-(C14-Pad+)") (class "Default")
      (node (ref "C14") (pin "+") (pinfunction "+_+") (pintype "passive"))
      (node (ref "R28") (pin "1") (pinfunction "1_1") (pintype "passive"))
    )
    (net (code "57") (name "Net-(C15-Pad+)") (class "Default")
      (node (ref "C15") (pin "+") (pinfunction "+_+") (pintype "passive"))
      (node (ref "R32") (pin "1") (pinfunction "1_1") (pintype "passive"))
    )
    (net (code "58") (name "Net-(C21-Pad-)") (class "Default")
      (node (ref "C21") (pin "-") (pinfunction "-_-") (pintype "passive"))
      (node (ref "R34") (pin "1") (pinfunction "1_1") (pintype "passive"))
    )
    (net (code "59") (name "Net-(C22-Pad-)") (class "Default")
      (node (ref "C22") (pin "-") (pinfunction "-_-") (pintype "passive"))
      (node (ref "R36") (pin "1") (pinfunction "1_1") (pintype "passive"))
    )
    (net (code "60") (name "Net-(IC1A--IN)") (class "Default")
      (node (ref "C3") (pin "1") (pinfunction "1_1") (pintype "passive"))
      (node (ref "IC1") (pin "2") (pinfunction "-IN_2") (pintype "input"))
      (node (ref "R13") (pin "2") (pinfunction "2_2") (pintype "passive"))
    )
    (net (code "61") (name "Net-(IC1A-OUT)") (class "Default")
      (node (ref "C3") (pin "2") (pinfunction "2_2") (pintype "passive"))
      (node (ref "IC1") (pin "1") (pinfunction "OUT_1") (pintype "output"))
      (node (ref "R14") (pin "2") (pinfunction "2_2") (pintype "passive"))
    )
    (net (code "62") (name "Net-(IC1B--IN)") (class "Default")
      (node (ref "C4") (pin "1") (pinfunction "1_1") (pintype "passive"))
      (node (ref "IC1") (pin "6") (pinfunction "-IN_6") (pintype "input"))
      (node (ref "R15") (pin "2") (pinfunction "2_2") (pintype "passive"))
    )
    (net (code "63") (name "Net-(IC1B-OUT)") (class "Default")
      (node (ref "C4") (pin "2") (pinfunction "2_2") (pintype "passive"))
      (node (ref "IC1") (pin "7") (pinfunction "OUT_7") (pintype "output"))
      (node (ref "R16") (pin "2") (pinfunction "2_2") (pintype "passive"))
    )
    (net (code "64") (name "Net-(IC1C-+IN)") (class "Default")
      (node (ref "C19") (pin "2") (pinfunction "2_2") (pintype "passive"))
      (node (ref "IC1") (pin "10") (pinfunction "+IN_10") (pintype "input"))
      (node (ref "R27") (pin "2") (pinfunction "2_2") (pintype "passive"))
    )
    (net (code "65") (name "Net-(IC1C--IN)") (class "Default")
      (node (ref "C17") (pin "1") (pinfunction "1_1") (pintype "passive"))
      (node (ref "IC1") (pin "9") (pinfunction "-IN_9") (pintype "input"))
      (node (ref "R26") (pin "2") (pinfunction "2_2") (pintype "passive"))
    )
    (net (code "66") (name "Net-(IC1C-OUT)") (class "Default")
      (node (ref "C17") (pin "2") (pinfunction "2_2") (pintype "passive"))
      (node (ref "C21") (pin "+") (pinfunction "+_+") (pintype "passive"))
      (node (ref "IC1") (pin "8") (pinfunction "OUT_8") (pintype "output"))
      (node (ref "R25") (pin "2") (pinfunction "2_2") (pintype "passive"))
      (node (ref "R33") (pin "1") (pinfunction "1_1") (pintype "passive"))
    )
    (net (code "67") (name "Net-(IC1D-+IN)") (class "Default")
      (node (ref "C20") (pin "2") (pinfunction "2_2") (pintype "passive"))
      (node (ref "IC1") (pin "12") (pinfunction "+IN_12") (pintype "input"))
      (node (ref "R31") (pin "2") (pinfunction "2_2") (pintype "passive"))
    )
    (net (code "68") (name "Net-(IC1D--IN)") (class "Default")
      (node (ref "C18") (pin "1") (pinfunction "1_1") (pintype "passive"))
      (node (ref "IC1") (pin "13") (pinfunction "-IN_13") (pintype "input"))
      (node (ref "R30") (pin "2") (pinfunction "2_2") (pintype "passive"))
    )
    (net (code "69") (name "Net-(IC1D-OUT)") (class "Default")
      (node (ref "C18") (pin "2") (pinfunction "2_2") (pintype "passive"))
      (node (ref "C22") (pin "+") (pinfunction "+_+") (pintype "passive"))
      (node (ref "IC1") (pin "14") (pinfunction "OUT_14") (pintype "output"))
      (node (ref "R29") (pin "2") (pinfunction "2_2") (pintype "passive"))
      (node (ref "R35") (pin "1") (pinfunction "1_1") (pintype "passive"))
    )
    (net (code "70") (name "Net-(J1-3)") (class "Default")
      (node (ref "J1") (pin "P$3") (pinfunction "3_P$3") (pintype "passive"))
      (node (ref "R42") (pin "1") (pinfunction "1_1") (pintype "passive"))
    )
    (net (code "71") (name "Net-(J1-4)") (class "Default")
      (node (ref "J1") (pin "P$2") (pinfunction "4_P$2") (pintype "passive"))
      (node (ref "R40") (pin "2") (pinfunction "2_2") (pintype "passive"))
    )
    (net (code "72") (name "Net-(J2-3)") (class "Default")
      (node (ref "J2") (pin "P$3") (pinfunction "3_P$3") (pintype "passive"))
      (node (ref "R1") (pin "1") (pinfunction "1_1") (pintype "passive"))
    )
    (net (code "73") (name "Net-(J3-3)") (class "Default")
      (node (ref "J3") (pin "P$3") (pinfunction "3_P$3") (pintype "passive"))
      (node (ref "R41") (pin "1") (pinfunction "1_1") (pintype "passive"))
    )
    (net (code "74") (name "Net-(J3-4)") (class "Default")
      (node (ref "J3") (pin "P$2") (pinfunction "4_P$2") (pintype "passive"))
      (node (ref "R39") (pin "2") (pinfunction "2_2") (pintype "passive"))
    )
    (net (code "75") (name "Net-(J4-3)") (class "Default")
      (node (ref "J4") (pin "P$3") (pinfunction "3_P$3") (pintype "passive"))
      (node (ref "R18") (pin "1") (pinfunction "1_1") (pintype "passive"))
    )
    (net (code "76") (name "Net-(J5-3)") (class "Default")
      (node (ref "J5") (pin "P$3") (pinfunction "3_P$3") (pintype "passive"))
      (node (ref "R12") (pin "1") (pinfunction "1_1") (pintype "passive"))
    )
    (net (code "77") (name "Net-(J6-3)") (class "Default")
      (node (ref "J6") (pin "P$3") (pinfunction "3_P$3") (pintype "passive"))
      (node (ref "R17") (pin "1") (pinfunction "1_1") (pintype "passive"))
    )
    (net (code "78") (name "Net-(JP1-Pad5)") (class "Default")
      (node (ref "JP1") (pin "5") (pinfunction "5_5") (pintype "passive"))
      (node (ref "R3") (pin "2") (pinfunction "2_2") (pintype "passive"))
    )
    (net (code "79") (name "Net-(JP13-Pad2)") (class "Default")
      (node (ref "JP13") (pin "2") (pinfunction "2_2") (pintype "passive"))
      (node (ref "X5") (pin "VBUS") (pinfunction "VBUS_VBUS") (pintype "bidirectional"))
    )
    (net (code "80") (name "Net-(LED1-CBLUE)") (class "Default")
      (node (ref "LED1") (pin "P4") (pinfunction "CBLUE_P4") (pintype "passive"))
      (node (ref "R10") (pin "2") (pinfunction "2_2") (pintype "passive"))
    )
    (net (code "81") (name "Net-(LED1-CGREEN)") (class "Default")
      (node (ref "LED1") (pin "P2") (pinfunction "CGREEN_P2") (pintype "passive"))
      (node (ref "R11") (pin "2") (pinfunction "2_2") (pintype "passive"))
    )
    (net (code "82") (name "Net-(LED1-CRED)") (class "Default")
      (node (ref "LED1") (pin "P1") (pinfunction "CRED_P1") (pintype "passive"))
      (node (ref "R9") (pin "2") (pinfunction "2_2") (pintype "passive"))
    )
    (net (code "83") (name "Net-(P1-Pad3)") (class "Default")
      (node (ref "P1") (pin "3") (pinfunction "3_3") (pintype "bidirectional"))
      (node (ref "R42") (pin "2") (pinfunction "2_2") (pintype "passive"))
    )
    (net (code "84") (name "Net-(P2-Pad3)") (class "Default")
      (node (ref "P2") (pin "3") (pinfunction "3_3") (pintype "bidirectional"))
      (node (ref "R41") (pin "2") (pinfunction "2_2") (pintype "passive"))
    )
    (net (code "85") (name "Net-(T1-B)") (class "Default")
      (node (ref "R1") (pin "2") (pinfunction "2_2") (pintype "passive"))
      (node (ref "R2") (pin "2") (pinfunction "2_2") (pintype "passive"))
      (node (ref "T1") (pin "2") (pinfunction "B_2") (pintype "passive"))
    )
    (net (code "86") (name "unconnected-(J2-4-PadP$2)") (class "Default")
      (node (ref "J2") (pin "P$2") (pinfunction "4_P$2") (pintype "passive"))
    )
    (net (code "87") (name "unconnected-(J7-PadGNDBREAK)") (class "Default")
      (node (ref "J7") (pin "GNDBREAK") (pinfunction "GNDBREAK_GNDBREAK") (pintype "bidirectional"))
    )
    (net (code "88") (name "unconnected-(X3-S1-PadM1)") (class "Default")
      (node (ref "X3") (pin "M1") (pinfunction "S1_M1") (pintype "passive"))
    )
    (net (code "89") (name "unconnected-(X3-S2-PadM2)") (class "Default")
      (node (ref "X3") (pin "M2") (pinfunction "S2_M2") (pintype "passive"))
    )
  )
)
